# TOP_BEE_Brother_1_3v.net
KiCad netlist of a schematic drawn in EAGLE
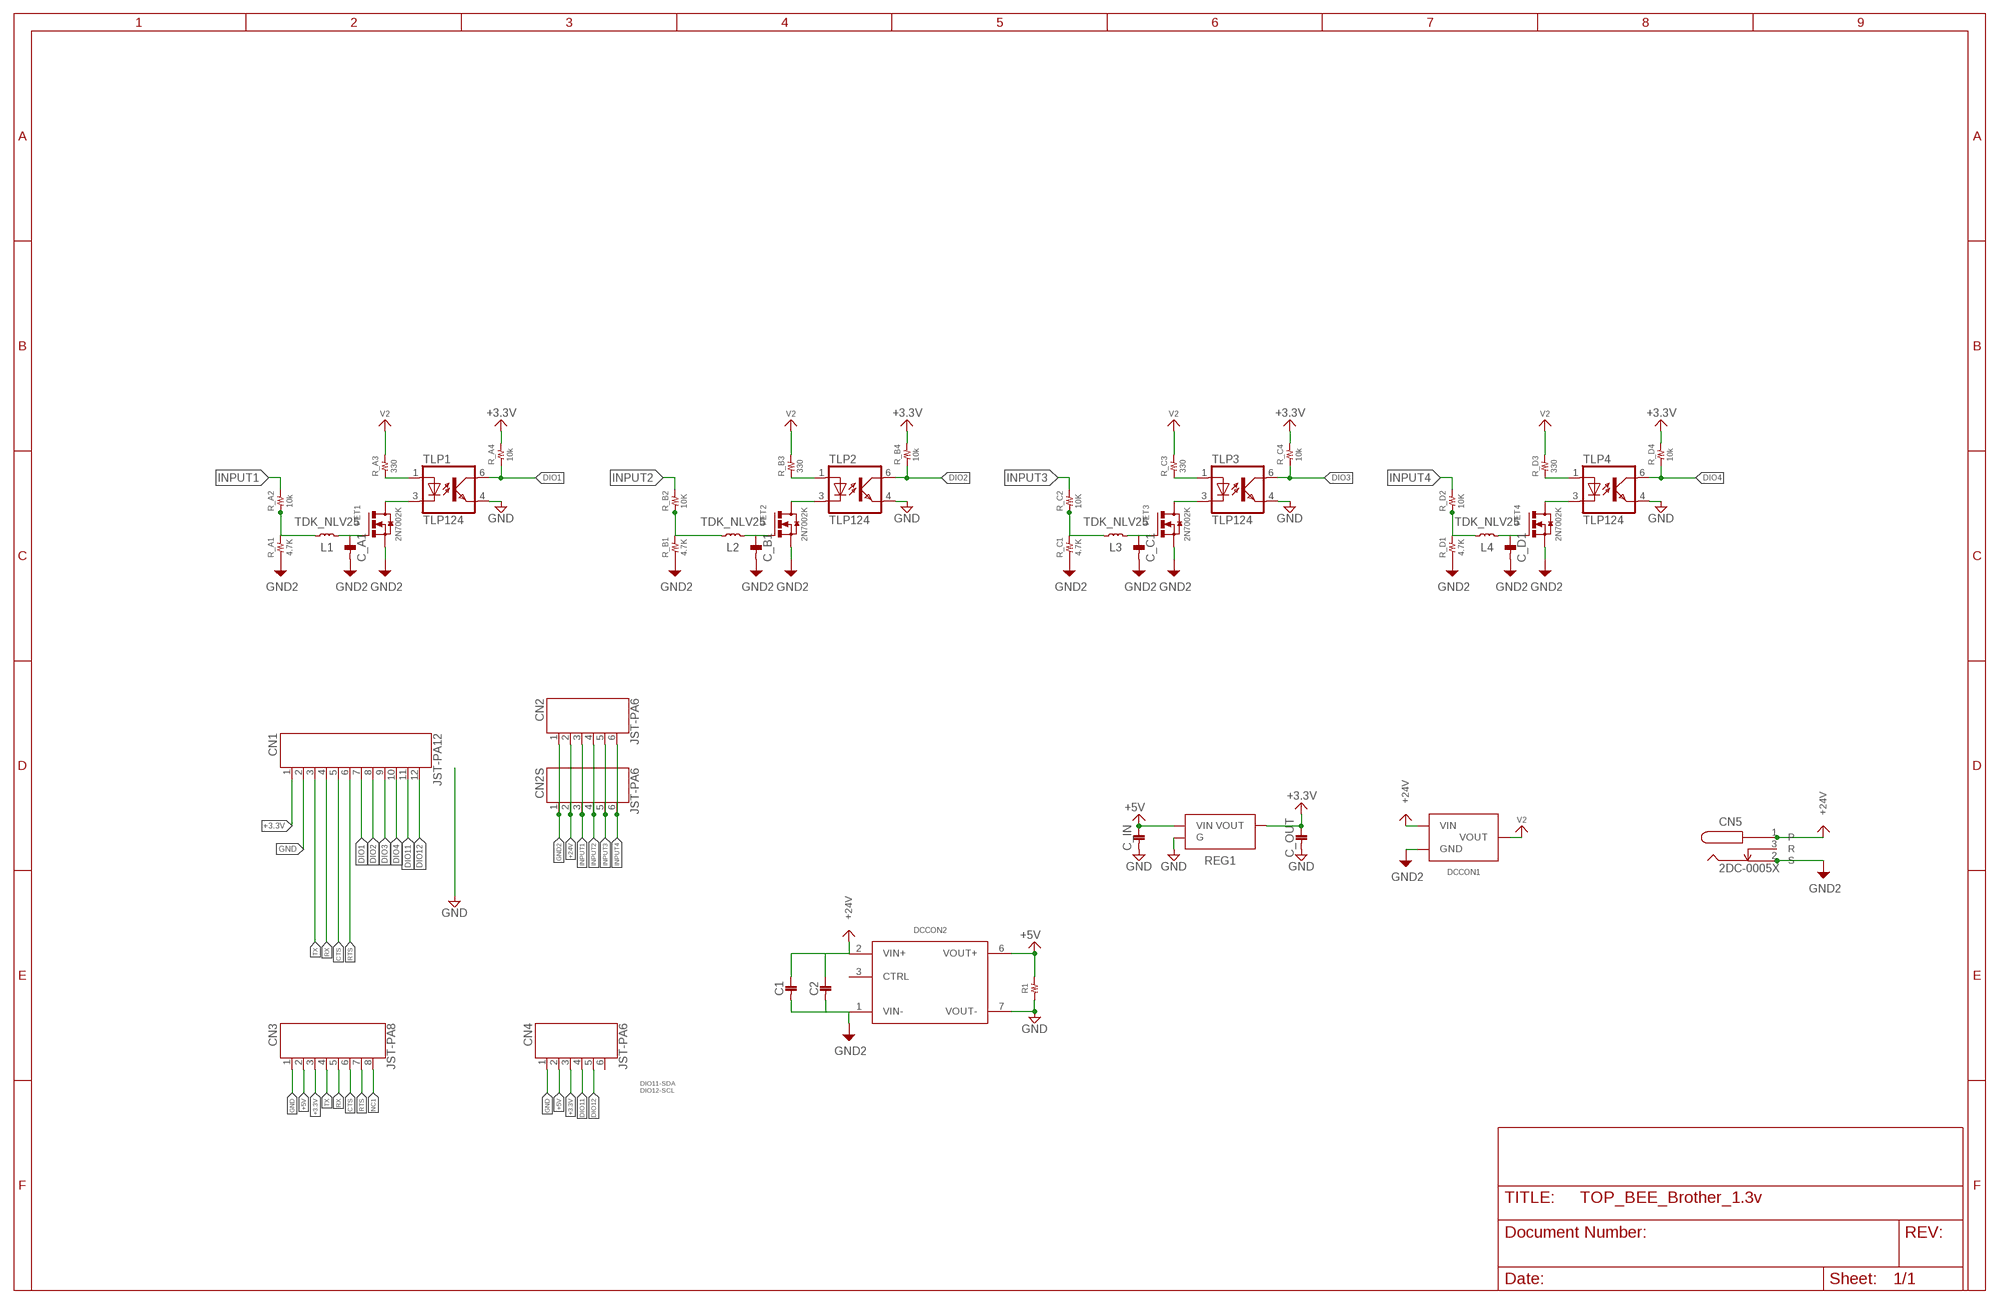
[diagram p0: schematic, sheet 1]

(export (version "E")
  (design (tool "Eeschema 10.0.6"))
  (components
    (comp (ref "C1")
      (value "3225")
      (footprint "eagle-import:3225")
      (libsource (lib "eagle-import") (part "3225"))
    )
    (comp (ref "C2")
      (value "1608")
      (footprint "eagle-import:1608")
      (libsource (lib "eagle-import") (part "1608"))
    )
    (comp (ref "CN1")
      (value "JST-PA12")
      (footprint "eagle-import:JST-PA12")
      (libsource (lib "eagle-import") (part "JST-PA12"))
    )
    (comp (ref "CN2")
      (value "JST-PA6")
      (footprint "eagle-import:JST-PA6")
      (libsource (lib "eagle-import") (part "JST-PA6"))
    )
    (comp (ref "CN2S")
      (value "JST-PA6")
      (footprint "eagle-import:JST-PA6")
      (libsource (lib "eagle-import") (part "JST-PA6"))
    )
    (comp (ref "CN3")
      (value "JST-PA8")
      (footprint "eagle-import:JST-PA8")
      (libsource (lib "eagle-import") (part "JST-PA8"))
    )
    (comp (ref "CN4")
      (value "JST-PA6")
      (footprint "eagle-import:JST-PA6")
      (libsource (lib "eagle-import") (part "JST-PA6"))
    )
    (comp (ref "CN5")
      (value "2DC-0005X")
      (footprint "eagle-import:2DC-0005D")
      (libsource (lib "eagle-import") (part "2DC-0005X"))
    )
    (comp (ref "C_A1")
      (value "1608")
      (footprint "eagle-import:1608")
      (libsource (lib "eagle-import") (part "1608"))
    )
    (comp (ref "C_B1")
      (value "1608")
      (footprint "eagle-import:1608")
      (libsource (lib "eagle-import") (part "1608"))
    )
    (comp (ref "C_C1")
      (value "1608")
      (footprint "eagle-import:1608")
      (libsource (lib "eagle-import") (part "1608"))
    )
    (comp (ref "C_D1")
      (value "1608")
      (footprint "eagle-import:1608")
      (libsource (lib "eagle-import") (part "1608"))
    )
    (comp (ref "C_IN")
      (value "1608")
      (footprint "eagle-import:1608")
      (libsource (lib "eagle-import") (part "1608"))
    )
    (comp (ref "C_OUT")
      (value "1608")
      (footprint "eagle-import:1608")
      (libsource (lib "eagle-import") (part "1608"))
    )
    (comp (ref "DCCON1")
      (value "Ｒ－７８Ｅ５．０")
      (footprint "eagle-import:Ｒ－７８Ｅ５．０")
      (libsource (lib "eagle-import") (part "Ｒ－７８Ｅ５．０"))
    )
    (comp (ref "DCCON2")
      (value "RS3")
      (footprint "eagle-import:SIP8")
      (libsource (lib "eagle-import") (part "RS3"))
    )
    (comp (ref "FET1")
      (value "2N7002K")
      (footprint "eagle-import:SOT23")
      (libsource (lib "eagle-import") (part "CHIP_FET"))
    )
    (comp (ref "FET2")
      (value "2N7002K")
      (footprint "eagle-import:SOT23")
      (libsource (lib "eagle-import") (part "CHIP_FET"))
    )
    (comp (ref "FET3")
      (value "2N7002K")
      (footprint "eagle-import:SOT23")
      (libsource (lib "eagle-import") (part "CHIP_FET"))
    )
    (comp (ref "FET4")
      (value "2N7002K")
      (footprint "eagle-import:SOT23")
      (libsource (lib "eagle-import") (part "CHIP_FET"))
    )
    (comp (ref "L1")
      (value "TDK_NLV25")
      (footprint "eagle-import:TDK_NLV")
      (libsource (lib "eagle-import") (part "TDK_NLV25"))
    )
    (comp (ref "L2")
      (value "TDK_NLV25")
      (footprint "eagle-import:TDK_NLV")
      (libsource (lib "eagle-import") (part "TDK_NLV25"))
    )
    (comp (ref "L3")
      (value "TDK_NLV25")
      (footprint "eagle-import:TDK_NLV")
      (libsource (lib "eagle-import") (part "TDK_NLV25"))
    )
    (comp (ref "L4")
      (value "TDK_NLV25")
      (footprint "eagle-import:TDK_NLV")
      (libsource (lib "eagle-import") (part "TDK_NLV25"))
    )
    (comp (ref "R1")
      (value "RESISTOR__SMD")
      (footprint "eagle-import:1608")
      (libsource (lib "eagle-import") (part "RESISTOR__SMD"))
    )
    (comp (ref "REG1")
      (value "NJM2845")
      (footprint "eagle-import:TO252")
      (libsource (lib "eagle-import") (part "NJM2845"))
    )
    (comp (ref "R_A1")
      (value "4.7K")
      (footprint "eagle-import:1608")
      (libsource (lib "eagle-import") (part "RESISTOR__SMD"))
    )
    (comp (ref "R_A2")
      (value "10k")
      (footprint "eagle-import:1608")
      (libsource (lib "eagle-import") (part "RESISTOR__SMD"))
    )
    (comp (ref "R_A3")
      (value "330")
      (footprint "eagle-import:1608")
      (libsource (lib "eagle-import") (part "RESISTOR__SMD"))
    )
    (comp (ref "R_A4")
      (value "10k")
      (footprint "eagle-import:1608")
      (libsource (lib "eagle-import") (part "RESISTOR__SMD"))
    )
    (comp (ref "R_B1")
      (value "4.7K")
      (footprint "eagle-import:1608")
      (libsource (lib "eagle-import") (part "RESISTOR__SMD"))
    )
    (comp (ref "R_B2")
      (value "10K")
      (footprint "eagle-import:1608")
      (libsource (lib "eagle-import") (part "RESISTOR__SMD"))
    )
    (comp (ref "R_B3")
      (value "330")
      (footprint "eagle-import:1608")
      (libsource (lib "eagle-import") (part "RESISTOR__SMD"))
    )
    (comp (ref "R_B4")
      (value "10k")
      (footprint "eagle-import:1608")
      (libsource (lib "eagle-import") (part "RESISTOR__SMD"))
    )
    (comp (ref "R_C1")
      (value "4.7K")
      (footprint "eagle-import:1608")
      (libsource (lib "eagle-import") (part "RESISTOR__SMD"))
    )
    (comp (ref "R_C2")
      (value "10K")
      (footprint "eagle-import:1608")
      (libsource (lib "eagle-import") (part "RESISTOR__SMD"))
    )
    (comp (ref "R_C3")
      (value "330")
      (footprint "eagle-import:1608")
      (libsource (lib "eagle-import") (part "RESISTOR__SMD"))
    )
    (comp (ref "R_C4")
      (value "10k")
      (footprint "eagle-import:1608")
      (libsource (lib "eagle-import") (part "RESISTOR__SMD"))
    )
    (comp (ref "R_D1")
      (value "4.7K")
      (footprint "eagle-import:1608")
      (libsource (lib "eagle-import") (part "RESISTOR__SMD"))
    )
    (comp (ref "R_D2")
      (value "10K")
      (footprint "eagle-import:1608")
      (libsource (lib "eagle-import") (part "RESISTOR__SMD"))
    )
    (comp (ref "R_D3")
      (value "330")
      (footprint "eagle-import:1608")
      (libsource (lib "eagle-import") (part "RESISTOR__SMD"))
    )
    (comp (ref "R_D4")
      (value "10k")
      (footprint "eagle-import:1608")
      (libsource (lib "eagle-import") (part "RESISTOR__SMD"))
    )
    (comp (ref "TLP1")
      (value "TLP124")
      (footprint "eagle-import:11−4C1")
      (libsource (lib "eagle-import") (part "TLP124"))
    )
    (comp (ref "TLP2")
      (value "TLP124")
      (footprint "eagle-import:11−4C1")
      (libsource (lib "eagle-import") (part "TLP124"))
    )
    (comp (ref "TLP3")
      (value "TLP124")
      (footprint "eagle-import:11−4C1")
      (libsource (lib "eagle-import") (part "TLP124"))
    )
    (comp (ref "TLP4")
      (value "TLP124")
      (footprint "eagle-import:11−4C1")
      (libsource (lib "eagle-import") (part "TLP124"))
    )
  )
  (nets
    (net (code "1") (name "+3.3V") (class "Default")
      (node (ref "CN1") (pin "1") (pinfunction "1_1") (pintype "passive"))
      (node (ref "CN3") (pin "3") (pinfunction "3_3") (pintype "passive"))
      (node (ref "CN4") (pin "3") (pinfunction "3_3") (pintype "passive"))
      (node (ref "C_OUT") (pin "P$1") (pinfunction "1_P$1") (pintype "passive"))
      (node (ref "REG1") (pin "3") (pinfunction "VOUT_3") (pintype "power_in"))
      (node (ref "R_A4") (pin "2") (pinfunction "P$2_2") (pintype "passive"))
      (node (ref "R_B4") (pin "2") (pinfunction "P$2_2") (pintype "passive"))
      (node (ref "R_C4") (pin "2") (pinfunction "P$2_2") (pintype "passive"))
      (node (ref "R_D4") (pin "2") (pinfunction "P$2_2") (pintype "passive"))
    )
    (net (code "2") (name "+5V") (class "Default")
      (node (ref "CN3") (pin "2") (pinfunction "2_2") (pintype "passive"))
      (node (ref "CN4") (pin "2") (pinfunction "2_2") (pintype "passive"))
      (node (ref "C_IN") (pin "P$1") (pinfunction "1_P$1") (pintype "passive"))
      (node (ref "DCCON2") (pin "6") (pinfunction "VOUT+_6") (pintype "bidirectional"))
      (node (ref "R1") (pin "2") (pinfunction "P$2_2") (pintype "passive"))
      (node (ref "REG1") (pin "1") (pinfunction "VIN_1") (pintype "power_in"))
    )
    (net (code "3") (name "+24V") (class "Default")
      (node (ref "C1") (pin "P$1") (pinfunction "1_P$1") (pintype "passive"))
      (node (ref "C2") (pin "P$1") (pinfunction "1_P$1") (pintype "passive"))
      (node (ref "CN2") (pin "2") (pinfunction "2_2") (pintype "passive"))
      (node (ref "CN2S") (pin "2") (pinfunction "2_2") (pintype "passive"))
      (node (ref "CN5") (pin "1") (pinfunction "P_1") (pintype "power_in"))
      (node (ref "DCCON1") (pin "1") (pinfunction "VIN_1") (pintype "bidirectional"))
      (node (ref "DCCON2") (pin "2") (pinfunction "VIN+_2") (pintype "bidirectional"))
    )
    (net (code "4") (name "CTS") (class "Default")
      (node (ref "CN1") (pin "5") (pinfunction "5_5") (pintype "passive"))
      (node (ref "CN3") (pin "6") (pinfunction "6_6") (pintype "passive"))
    )
    (net (code "5") (name "DIO1") (class "Default")
      (node (ref "CN1") (pin "7") (pinfunction "7_7") (pintype "passive"))
      (node (ref "R_A4") (pin "1") (pinfunction "P$1_1") (pintype "passive"))
      (node (ref "TLP1") (pin "6") (pinfunction "COL_6") (pintype "passive"))
    )
    (net (code "6") (name "DIO2") (class "Default")
      (node (ref "CN1") (pin "8") (pinfunction "8_8") (pintype "passive"))
      (node (ref "R_B4") (pin "1") (pinfunction "P$1_1") (pintype "passive"))
      (node (ref "TLP2") (pin "6") (pinfunction "COL_6") (pintype "passive"))
    )
    (net (code "7") (name "DIO3") (class "Default")
      (node (ref "CN1") (pin "9") (pinfunction "9_9") (pintype "passive"))
      (node (ref "R_C4") (pin "1") (pinfunction "P$1_1") (pintype "passive"))
      (node (ref "TLP3") (pin "6") (pinfunction "COL_6") (pintype "passive"))
    )
    (net (code "8") (name "DIO4") (class "Default")
      (node (ref "CN1") (pin "10") (pinfunction "10_10") (pintype "passive"))
      (node (ref "R_D4") (pin "1") (pinfunction "P$1_1") (pintype "passive"))
      (node (ref "TLP4") (pin "6") (pinfunction "COL_6") (pintype "passive"))
    )
    (net (code "9") (name "DIO11") (class "Default")
      (node (ref "CN1") (pin "11") (pinfunction "11_11") (pintype "passive"))
      (node (ref "CN4") (pin "4") (pinfunction "4_4") (pintype "passive"))
    )
    (net (code "10") (name "DIO12") (class "Default")
      (node (ref "CN1") (pin "12") (pinfunction "12_12") (pintype "passive"))
      (node (ref "CN4") (pin "5") (pinfunction "5_5") (pintype "passive"))
    )
    (net (code "11") (name "GND") (class "Default")
      (node (ref "CN1") (pin "2") (pinfunction "2_2") (pintype "passive"))
      (node (ref "CN3") (pin "1") (pinfunction "1_1") (pintype "passive"))
      (node (ref "CN4") (pin "1") (pinfunction "1_1") (pintype "passive"))
      (node (ref "C_IN") (pin "P$2") (pinfunction "2_P$2") (pintype "passive"))
      (node (ref "C_OUT") (pin "P$2") (pinfunction "2_P$2") (pintype "passive"))
      (node (ref "DCCON2") (pin "7") (pinfunction "VOUT-_7") (pintype "bidirectional"))
      (node (ref "R1") (pin "1") (pinfunction "P$1_1") (pintype "passive"))
      (node (ref "REG1") (pin "2") (pinfunction "G_2") (pintype "power_in"))
      (node (ref "TLP1") (pin "4") (pinfunction "EMIT_4") (pintype "passive"))
      (node (ref "TLP2") (pin "4") (pinfunction "EMIT_4") (pintype "passive"))
      (node (ref "TLP3") (pin "4") (pinfunction "EMIT_4") (pintype "passive"))
      (node (ref "TLP4") (pin "4") (pinfunction "EMIT_4") (pintype "passive"))
    )
    (net (code "12") (name "GND2") (class "Default")
      (node (ref "C1") (pin "P$2") (pinfunction "2_P$2") (pintype "passive"))
      (node (ref "C2") (pin "P$2") (pinfunction "2_P$2") (pintype "passive"))
      (node (ref "CN2") (pin "1") (pinfunction "1_1") (pintype "passive"))
      (node (ref "CN2S") (pin "1") (pinfunction "1_1") (pintype "passive"))
      (node (ref "CN5") (pin "2") (pinfunction "S_2") (pintype "power_in"))
      (node (ref "C_A1") (pin "P$2") (pinfunction "2_P$2") (pintype "passive"))
      (node (ref "C_B1") (pin "P$2") (pinfunction "2_P$2") (pintype "passive"))
      (node (ref "C_C1") (pin "P$2") (pinfunction "2_P$2") (pintype "passive"))
      (node (ref "C_D1") (pin "P$2") (pinfunction "2_P$2") (pintype "passive"))
      (node (ref "DCCON1") (pin "2") (pinfunction "GND_2") (pintype "bidirectional"))
      (node (ref "DCCON2") (pin "1") (pinfunction "VIN-_1") (pintype "bidirectional"))
      (node (ref "FET1") (pin "2") (pinfunction "S_2") (pintype "passive"))
      (node (ref "FET2") (pin "2") (pinfunction "S_2") (pintype "passive"))
      (node (ref "FET3") (pin "2") (pinfunction "S_2") (pintype "passive"))
      (node (ref "FET4") (pin "2") (pinfunction "S_2") (pintype "passive"))
      (node (ref "R_A1") (pin "1") (pinfunction "P$1_1") (pintype "passive"))
      (node (ref "R_B1") (pin "1") (pinfunction "P$1_1") (pintype "passive"))
      (node (ref "R_C1") (pin "1") (pinfunction "P$1_1") (pintype "passive"))
      (node (ref "R_D1") (pin "1") (pinfunction "P$1_1") (pintype "passive"))
    )
    (net (code "13") (name "INPUT1") (class "Default")
      (node (ref "CN2") (pin "3") (pinfunction "3_3") (pintype "passive"))
      (node (ref "CN2S") (pin "3") (pinfunction "3_3") (pintype "passive"))
      (node (ref "R_A2") (pin "2") (pinfunction "P$2_2") (pintype "passive"))
    )
    (net (code "14") (name "INPUT2") (class "Default")
      (node (ref "CN2") (pin "4") (pinfunction "4_4") (pintype "passive"))
      (node (ref "CN2S") (pin "4") (pinfunction "4_4") (pintype "passive"))
      (node (ref "R_B2") (pin "2") (pinfunction "P$2_2") (pintype "passive"))
    )
    (net (code "15") (name "INPUT3") (class "Default")
      (node (ref "CN2") (pin "5") (pinfunction "5_5") (pintype "passive"))
      (node (ref "CN2S") (pin "5") (pinfunction "5_5") (pintype "passive"))
      (node (ref "R_C2") (pin "2") (pinfunction "P$2_2") (pintype "passive"))
    )
    (net (code "16") (name "INPUT4") (class "Default")
      (node (ref "CN2") (pin "6") (pinfunction "6_6") (pintype "passive"))
      (node (ref "CN2S") (pin "6") (pinfunction "6_6") (pintype "passive"))
      (node (ref "R_D2") (pin "2") (pinfunction "P$2_2") (pintype "passive"))
    )
    (net (code "17") (name "NC1") (class "Default")
      (node (ref "CN3") (pin "8") (pinfunction "8_8") (pintype "passive"))
    )
    (net (code "18") (name "Net-(C_A1-1)") (class "Default")
      (node (ref "C_A1") (pin "P$1") (pinfunction "1_P$1") (pintype "passive"))
      (node (ref "FET1") (pin "1") (pinfunction "G_1") (pintype "passive"))
      (node (ref "L1") (pin "P$2") (pinfunction "2_P$2") (pintype "passive"))
    )
    (net (code "19") (name "Net-(C_B1-1)") (class "Default")
      (node (ref "C_B1") (pin "P$1") (pinfunction "1_P$1") (pintype "passive"))
      (node (ref "FET2") (pin "1") (pinfunction "G_1") (pintype "passive"))
      (node (ref "L2") (pin "P$2") (pinfunction "2_P$2") (pintype "passive"))
    )
    (net (code "20") (name "Net-(C_C1-1)") (class "Default")
      (node (ref "C_C1") (pin "P$1") (pinfunction "1_P$1") (pintype "passive"))
      (node (ref "FET3") (pin "1") (pinfunction "G_1") (pintype "passive"))
      (node (ref "L3") (pin "P$2") (pinfunction "2_P$2") (pintype "passive"))
    )
    (net (code "21") (name "Net-(C_D1-1)") (class "Default")
      (node (ref "C_D1") (pin "P$1") (pinfunction "1_P$1") (pintype "passive"))
      (node (ref "FET4") (pin "1") (pinfunction "G_1") (pintype "passive"))
      (node (ref "L4") (pin "P$2") (pinfunction "2_P$2") (pintype "passive"))
    )
    (net (code "22") (name "Net-(FET1-D)") (class "Default")
      (node (ref "FET1") (pin "3") (pinfunction "D_3") (pintype "passive"))
      (node (ref "TLP1") (pin "3") (pinfunction "C_3") (pintype "passive"))
    )
    (net (code "23") (name "Net-(FET2-D)") (class "Default")
      (node (ref "FET2") (pin "3") (pinfunction "D_3") (pintype "passive"))
      (node (ref "TLP2") (pin "3") (pinfunction "C_3") (pintype "passive"))
    )
    (net (code "24") (name "Net-(FET3-D)") (class "Default")
      (node (ref "FET3") (pin "3") (pinfunction "D_3") (pintype "passive"))
      (node (ref "TLP3") (pin "3") (pinfunction "C_3") (pintype "passive"))
    )
    (net (code "25") (name "Net-(FET4-D)") (class "Default")
      (node (ref "FET4") (pin "3") (pinfunction "D_3") (pintype "passive"))
      (node (ref "TLP4") (pin "3") (pinfunction "C_3") (pintype "passive"))
    )
    (net (code "26") (name "Net-(L1-1)") (class "Default")
      (node (ref "L1") (pin "P$1") (pinfunction "1_P$1") (pintype "passive"))
      (node (ref "R_A1") (pin "2") (pinfunction "P$2_2") (pintype "passive"))
      (node (ref "R_A2") (pin "1") (pinfunction "P$1_1") (pintype "passive"))
    )
    (net (code "27") (name "Net-(L2-1)") (class "Default")
      (node (ref "L2") (pin "P$1") (pinfunction "1_P$1") (pintype "passive"))
      (node (ref "R_B1") (pin "2") (pinfunction "P$2_2") (pintype "passive"))
      (node (ref "R_B2") (pin "1") (pinfunction "P$1_1") (pintype "passive"))
    )
    (net (code "28") (name "Net-(L3-1)") (class "Default")
      (node (ref "L3") (pin "P$1") (pinfunction "1_P$1") (pintype "passive"))
      (node (ref "R_C1") (pin "2") (pinfunction "P$2_2") (pintype "passive"))
      (node (ref "R_C2") (pin "1") (pinfunction "P$1_1") (pintype "passive"))
    )
    (net (code "29") (name "Net-(L4-1)") (class "Default")
      (node (ref "L4") (pin "P$1") (pinfunction "1_P$1") (pintype "passive"))
      (node (ref "R_D1") (pin "2") (pinfunction "P$2_2") (pintype "passive"))
      (node (ref "R_D2") (pin "1") (pinfunction "P$1_1") (pintype "passive"))
    )
    (net (code "30") (name "Net-(R_A3-P$1)") (class "Default")
      (node (ref "R_A3") (pin "1") (pinfunction "P$1_1") (pintype "passive"))
      (node (ref "TLP1") (pin "1") (pinfunction "A_1") (pintype "passive"))
    )
    (net (code "31") (name "Net-(R_B3-P$1)") (class "Default")
      (node (ref "R_B3") (pin "1") (pinfunction "P$1_1") (pintype "passive"))
      (node (ref "TLP2") (pin "1") (pinfunction "A_1") (pintype "passive"))
    )
    (net (code "32") (name "Net-(R_C3-P$1)") (class "Default")
      (node (ref "R_C3") (pin "1") (pinfunction "P$1_1") (pintype "passive"))
      (node (ref "TLP3") (pin "1") (pinfunction "A_1") (pintype "passive"))
    )
    (net (code "33") (name "Net-(R_D3-P$1)") (class "Default")
      (node (ref "R_D3") (pin "1") (pinfunction "P$1_1") (pintype "passive"))
      (node (ref "TLP4") (pin "1") (pinfunction "A_1") (pintype "passive"))
    )
    (net (code "34") (name "RTS") (class "Default")
      (node (ref "CN1") (pin "6") (pinfunction "6_6") (pintype "passive"))
      (node (ref "CN3") (pin "7") (pinfunction "7_7") (pintype "passive"))
    )
    (net (code "35") (name "RX") (class "Default")
      (node (ref "CN1") (pin "4") (pinfunction "4_4") (pintype "passive"))
      (node (ref "CN3") (pin "5") (pinfunction "5_5") (pintype "passive"))
    )
    (net (code "36") (name "TX") (class "Default")
      (node (ref "CN1") (pin "3") (pinfunction "3_3") (pintype "passive"))
      (node (ref "CN3") (pin "4") (pinfunction "4_4") (pintype "passive"))
    )
    (net (code "37") (name "V2") (class "Default")
      (node (ref "DCCON1") (pin "3") (pinfunction "VOUT_3") (pintype "bidirectional"))
      (node (ref "R_A3") (pin "2") (pinfunction "P$2_2") (pintype "passive"))
      (node (ref "R_B3") (pin "2") (pinfunction "P$2_2") (pintype "passive"))
      (node (ref "R_C3") (pin "2") (pinfunction "P$2_2") (pintype "passive"))
      (node (ref "R_D3") (pin "2") (pinfunction "P$2_2") (pintype "passive"))
    )
    (net (code "38") (name "unconnected-(CN4-Pad6)") (class "Default")
      (node (ref "CN4") (pin "6") (pinfunction "6_6") (pintype "passive"))
    )
    (net (code "39") (name "unconnected-(CN5-R-Pad3)") (class "Default")
      (node (ref "CN5") (pin "3") (pinfunction "R_3") (pintype "input"))
    )
    (net (code "40") (name "unconnected-(DCCON2-CTRL-Pad3)") (class "Default")
      (node (ref "DCCON2") (pin "3") (pinfunction "CTRL_3") (pintype "bidirectional"))
    )
  )
)
